# FlowControllerNChannel.net
KiCad netlist of a schematic drawn in EAGLE
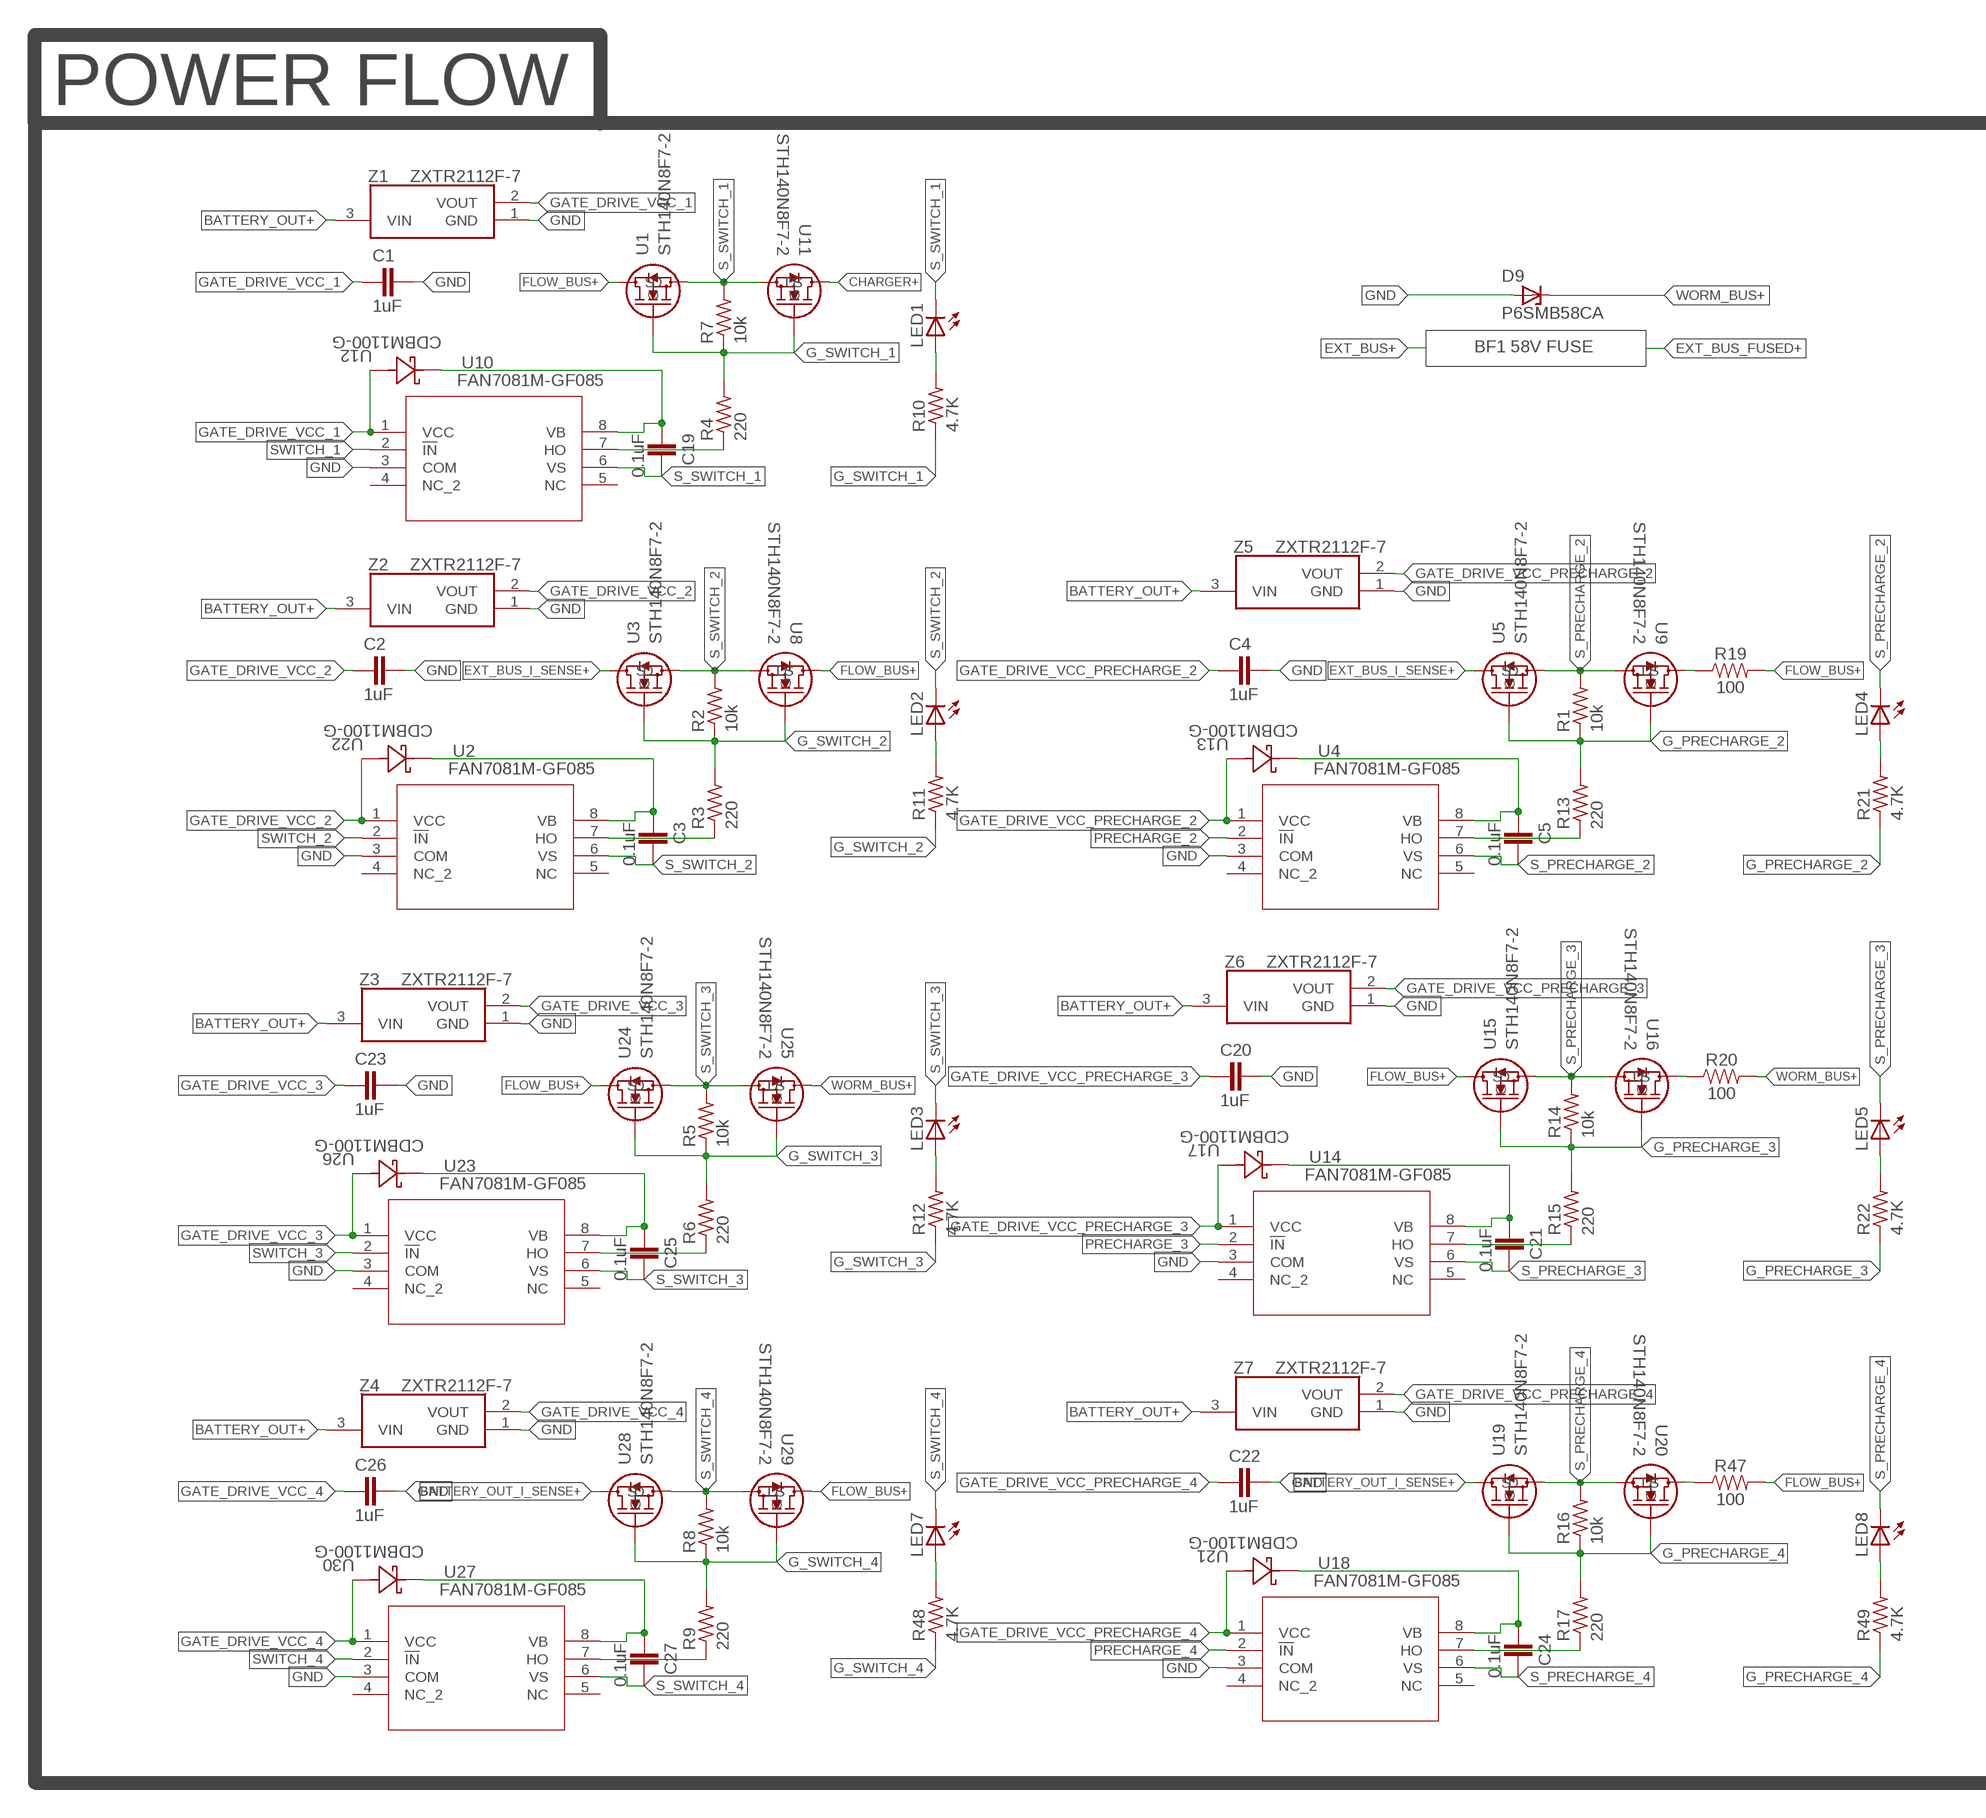
[diagram p0: schematic, sheet 1, part 1 of 2]
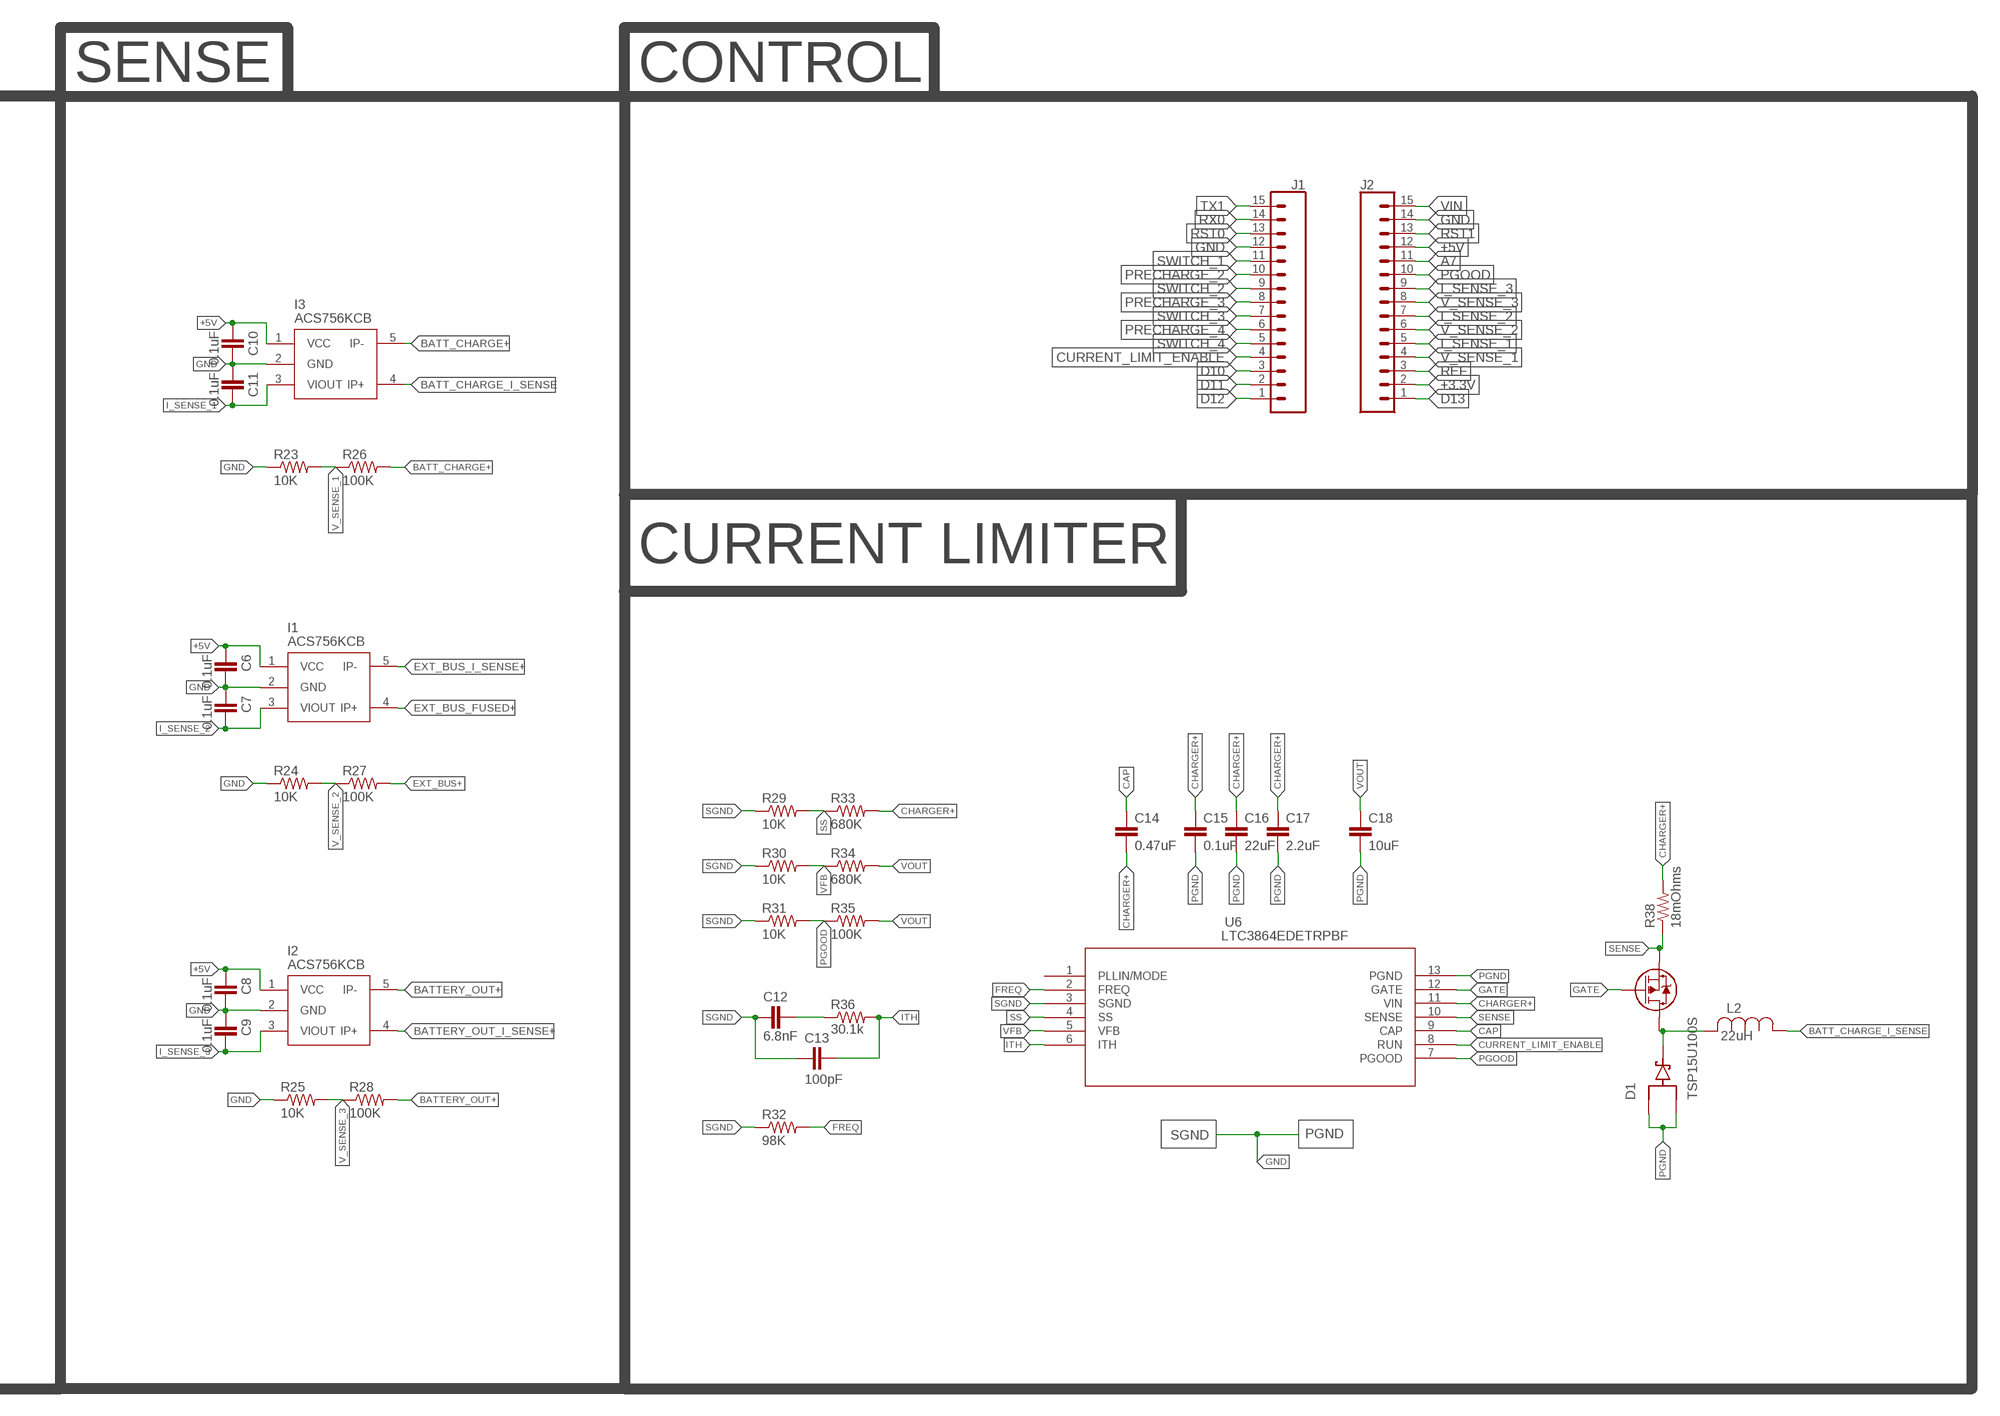
[diagram p1: schematic, sheet 1, part 2 of 2]

(export (version "E")
  (design (tool "Eeschema 10.0.6"))
  (components
    (comp (ref "C1")
      (value "1uF")
      (footprint "eagle-import:0805")
      (libsource (lib "eagle-import") (part "2.2UF-0805-25V-(+80/-20%)"))
    )
    (comp (ref "C2")
      (value "1uF")
      (footprint "eagle-import:0805")
      (libsource (lib "eagle-import") (part "2.2UF-0805-25V-(+80/-20%)"))
    )
    (comp (ref "C3")
      (value "0.1uF")
      (footprint "eagle-import:0805")
      (libsource (lib "eagle-import") (part "2.2UF-0805-25V-(+80/-20%)"))
    )
    (comp (ref "C4")
      (value "1uF")
      (footprint "eagle-import:0805")
      (libsource (lib "eagle-import") (part "2.2UF-0805-25V-(+80/-20%)"))
    )
    (comp (ref "C5")
      (value "0.1uF")
      (footprint "eagle-import:0805")
      (libsource (lib "eagle-import") (part "2.2UF-0805-25V-(+80/-20%)"))
    )
    (comp (ref "C6")
      (value "0.1uF")
      (footprint "eagle-import:0805")
      (libsource (lib "eagle-import") (part "2.2UF-0805-25V-(+80/-20%)"))
    )
    (comp (ref "C7")
      (value "0.1uF")
      (footprint "eagle-import:0805")
      (libsource (lib "eagle-import") (part "2.2UF-0805-25V-(+80/-20%)"))
    )
    (comp (ref "C8")
      (value "0.1uF")
      (footprint "eagle-import:0805")
      (libsource (lib "eagle-import") (part "2.2UF-0805-25V-(+80/-20%)"))
    )
    (comp (ref "C9")
      (value "0.1uF")
      (footprint "eagle-import:0805")
      (libsource (lib "eagle-import") (part "2.2UF-0805-25V-(+80/-20%)"))
    )
    (comp (ref "C10")
      (value "0.1uF")
      (footprint "eagle-import:0805")
      (libsource (lib "eagle-import") (part "2.2UF-0805-25V-(+80/-20%)"))
    )
    (comp (ref "C11")
      (value "0.1uF")
      (footprint "eagle-import:0805")
      (libsource (lib "eagle-import") (part "2.2UF-0805-25V-(+80/-20%)"))
    )
    (comp (ref "C12")
      (value "6.8nF")
      (footprint "eagle-import:0805")
      (libsource (lib "eagle-import") (part "2.2UF-0805-25V-(+80/-20%)"))
    )
    (comp (ref "C13")
      (value "100pF")
      (footprint "eagle-import:0805")
      (libsource (lib "eagle-import") (part "2.2UF-0805-25V-(+80/-20%)"))
    )
    (comp (ref "C14")
      (value "0.47uF")
      (footprint "eagle-import:0805")
      (libsource (lib "eagle-import") (part "2.2UF-0805-25V-(+80/-20%)"))
    )
    (comp (ref "C15")
      (value "0.1uF")
      (footprint "eagle-import:0805")
      (libsource (lib "eagle-import") (part "2.2UF-0805-25V-(+80/-20%)"))
    )
    (comp (ref "C16")
      (value "22uF")
      (footprint "eagle-import:1210")
      (libsource (lib "eagle-import") (part "10UF-1210-50V-20%"))
    )
    (comp (ref "C17")
      (value "2.2uF")
      (footprint "eagle-import:1210")
      (libsource (lib "eagle-import") (part "10UF-1210-50V-20%"))
    )
    (comp (ref "C18")
      (value "10uF")
      (footprint "eagle-import:1210")
      (libsource (lib "eagle-import") (part "10UF-1210-50V-20%"))
    )
    (comp (ref "C19")
      (value "0.1uF")
      (footprint "eagle-import:0805")
      (libsource (lib "eagle-import") (part "2.2UF-0805-25V-(+80/-20%)"))
    )
    (comp (ref "C20")
      (value "1uF")
      (footprint "eagle-import:0805")
      (libsource (lib "eagle-import") (part "2.2UF-0805-25V-(+80/-20%)"))
    )
    (comp (ref "C21")
      (value "0.1uF")
      (footprint "eagle-import:0805")
      (libsource (lib "eagle-import") (part "2.2UF-0805-25V-(+80/-20%)"))
    )
    (comp (ref "C22")
      (value "1uF")
      (footprint "eagle-import:0805")
      (libsource (lib "eagle-import") (part "2.2UF-0805-25V-(+80/-20%)"))
    )
    (comp (ref "C23")
      (value "1uF")
      (footprint "eagle-import:0805")
      (libsource (lib "eagle-import") (part "2.2UF-0805-25V-(+80/-20%)"))
    )
    (comp (ref "C24")
      (value "0.1uF")
      (footprint "eagle-import:0805")
      (libsource (lib "eagle-import") (part "2.2UF-0805-25V-(+80/-20%)"))
    )
    (comp (ref "C25")
      (value "0.1uF")
      (footprint "eagle-import:0805")
      (libsource (lib "eagle-import") (part "2.2UF-0805-25V-(+80/-20%)"))
    )
    (comp (ref "C26")
      (value "1uF")
      (footprint "eagle-import:0805")
      (libsource (lib "eagle-import") (part "2.2UF-0805-25V-(+80/-20%)"))
    )
    (comp (ref "C27")
      (value "0.1uF")
      (footprint "eagle-import:0805")
      (libsource (lib "eagle-import") (part "2.2UF-0805-25V-(+80/-20%)"))
    )
    (comp (ref "D1")
      (value "TSP15U100S")
      (footprint "eagle-import:DIO_TSP15U100S")
      (fields
        (field (name "DIGI-KEY_PART_NUMBER") "1801-TSP15U100STR-ND")
        (field (name "MF") "Taiwan Semiconductor")
      )
      (libsource (lib "eagle-import") (part "TSP15U100S"))
    )
    (comp (ref "D9")
      (value "P6SMB58CA")
      (footprint "eagle-import:DO214AA")
      (fields (field (name "MF") "ON Semiconductor") (field (name "MPN") "1SMB5913BT3G"))
      (libsource (lib "eagle-import") (part "1SMB59BT3G13"))
    )
    (comp (ref "I1")
      (value "ACS756KCB")
      (footprint "eagle-import:ACS756KCB")
      (libsource (lib "eagle-import") (part "ACS756KCB"))
    )
    (comp (ref "I2")
      (value "ACS756KCB")
      (footprint "eagle-import:ACS756KCB")
      (libsource (lib "eagle-import") (part "ACS756KCB"))
    )
    (comp (ref "I3")
      (value "ACS756KCB")
      (footprint "eagle-import:ACS756KCB")
      (libsource (lib "eagle-import") (part "ACS756KCB"))
    )
    (comp (ref "J1")
      (value "CONN_15")
      (footprint "eagle-import:1X15")
      (libsource (lib "eagle-import") (part "CONN_15"))
    )
    (comp (ref "J2")
      (value "CONN_15")
      (footprint "eagle-import:1X15")
      (fields (field (name "SPICEPREFIX") "X"))
      (libsource (lib "eagle-import") (part "CONN_15"))
    )
    (comp (ref "L2")
      (value "22uH")
      (footprint "eagle-import:IND_IHLP-4040DZ_VIS")
      (fields
        (field (name "MANUFACTURER_PART_NUMBER") "IHLP4040DZER6R8M01")
        (field (name "COPYRIGHT") "Copyright (C) 2022 Ultra Librarian. All rights reserved.")
      )
      (libsource (lib "eagle-import") (part "IHLP4040DZER6R8M01"))
    )
    (comp (ref "LED1")
      (value "LEDCHIPLED_0805")
      (footprint "eagle-import:CHIPLED_0805")
      (libsource (lib "eagle-import") (part "LEDCHIPLED_0805"))
    )
    (comp (ref "LED2")
      (value "LEDCHIPLED_0805")
      (footprint "eagle-import:CHIPLED_0805")
      (libsource (lib "eagle-import") (part "LEDCHIPLED_0805"))
    )
    (comp (ref "LED3")
      (value "LEDCHIPLED_0805")
      (footprint "eagle-import:CHIPLED_0805")
      (libsource (lib "eagle-import") (part "LEDCHIPLED_0805"))
    )
    (comp (ref "LED4")
      (value "LEDCHIPLED_0805")
      (footprint "eagle-import:CHIPLED_0805")
      (libsource (lib "eagle-import") (part "LEDCHIPLED_0805"))
    )
    (comp (ref "LED5")
      (value "LEDCHIPLED_0805")
      (footprint "eagle-import:CHIPLED_0805")
      (libsource (lib "eagle-import") (part "LEDCHIPLED_0805"))
    )
    (comp (ref "LED7")
      (value "LEDCHIPLED_0805")
      (footprint "eagle-import:CHIPLED_0805")
      (libsource (lib "eagle-import") (part "LEDCHIPLED_0805"))
    )
    (comp (ref "LED8")
      (value "LEDCHIPLED_0805")
      (footprint "eagle-import:CHIPLED_0805")
      (libsource (lib "eagle-import") (part "LEDCHIPLED_0805"))
    )
    (comp (ref "R1")
      (value "10k")
      (footprint "eagle-import:M0805")
      (libsource (lib "eagle-import") (part "R-US_M0805"))
    )
    (comp (ref "R2")
      (value "10k")
      (footprint "eagle-import:M0805")
      (libsource (lib "eagle-import") (part "R-US_M0805"))
    )
    (comp (ref "R3")
      (value "220")
      (footprint "eagle-import:M0805")
      (libsource (lib "eagle-import") (part "R-US_M0805"))
    )
    (comp (ref "R4")
      (value "220")
      (footprint "eagle-import:M0805")
      (libsource (lib "eagle-import") (part "R-US_M0805"))
    )
    (comp (ref "R5")
      (value "10k")
      (footprint "eagle-import:M0805")
      (libsource (lib "eagle-import") (part "R-US_M0805"))
    )
    (comp (ref "R6")
      (value "220")
      (footprint "eagle-import:M0805")
      (libsource (lib "eagle-import") (part "R-US_M0805"))
    )
    (comp (ref "R7")
      (value "10k")
      (footprint "eagle-import:M0805")
      (libsource (lib "eagle-import") (part "R-US_M0805"))
    )
    (comp (ref "R8")
      (value "10k")
      (footprint "eagle-import:M0805")
      (libsource (lib "eagle-import") (part "R-US_M0805"))
    )
    (comp (ref "R9")
      (value "220")
      (footprint "eagle-import:M0805")
      (libsource (lib "eagle-import") (part "R-US_M0805"))
    )
    (comp (ref "R10")
      (value "4.7K")
      (footprint "eagle-import:M0805")
      (libsource (lib "eagle-import") (part "R-US_M0805"))
    )
    (comp (ref "R11")
      (value "4.7K")
      (footprint "eagle-import:M0805")
      (libsource (lib "eagle-import") (part "R-US_M0805"))
    )
    (comp (ref "R12")
      (value "4.7K")
      (footprint "eagle-import:M0805")
      (libsource (lib "eagle-import") (part "R-US_M0805"))
    )
    (comp (ref "R13")
      (value "220")
      (footprint "eagle-import:M0805")
      (libsource (lib "eagle-import") (part "R-US_M0805"))
    )
    (comp (ref "R14")
      (value "10k")
      (footprint "eagle-import:M0805")
      (libsource (lib "eagle-import") (part "R-US_M0805"))
    )
    (comp (ref "R15")
      (value "220")
      (footprint "eagle-import:M0805")
      (libsource (lib "eagle-import") (part "R-US_M0805"))
    )
    (comp (ref "R16")
      (value "10k")
      (footprint "eagle-import:M0805")
      (libsource (lib "eagle-import") (part "R-US_M0805"))
    )
    (comp (ref "R17")
      (value "220")
      (footprint "eagle-import:M0805")
      (libsource (lib "eagle-import") (part "R-US_M0805"))
    )
    (comp (ref "R19")
      (value "100")
      (footprint "eagle-import:2512")
      (libsource (lib "eagle-import") (part "0.05OHM-2512-3W-1%"))
    )
    (comp (ref "R20")
      (value "100")
      (footprint "eagle-import:2512")
      (libsource (lib "eagle-import") (part "0.05OHM-2512-3W-1%"))
    )
    (comp (ref "R21")
      (value "4.7K")
      (footprint "eagle-import:M0805")
      (libsource (lib "eagle-import") (part "R-US_M0805"))
    )
    (comp (ref "R22")
      (value "4.7K")
      (footprint "eagle-import:M0805")
      (libsource (lib "eagle-import") (part "R-US_M0805"))
    )
    (comp (ref "R23")
      (value "10K")
      (footprint "eagle-import:M0805")
      (libsource (lib "eagle-import") (part "R-US_M0805"))
    )
    (comp (ref "R24")
      (value "10K")
      (footprint "eagle-import:M0805")
      (libsource (lib "eagle-import") (part "R-US_M0805"))
    )
    (comp (ref "R25")
      (value "10K")
      (footprint "eagle-import:M0805")
      (libsource (lib "eagle-import") (part "R-US_M0805"))
    )
    (comp (ref "R26")
      (value "100K")
      (footprint "eagle-import:M0805")
      (libsource (lib "eagle-import") (part "R-US_M0805"))
    )
    (comp (ref "R27")
      (value "100K")
      (footprint "eagle-import:M0805")
      (libsource (lib "eagle-import") (part "R-US_M0805"))
    )
    (comp (ref "R28")
      (value "100K")
      (footprint "eagle-import:M0805")
      (libsource (lib "eagle-import") (part "R-US_M0805"))
    )
    (comp (ref "R29")
      (value "10K")
      (footprint "eagle-import:M0805")
      (libsource (lib "eagle-import") (part "R-US_M0805"))
    )
    (comp (ref "R30")
      (value "10K")
      (footprint "eagle-import:M0805")
      (libsource (lib "eagle-import") (part "R-US_M0805"))
    )
    (comp (ref "R31")
      (value "10K")
      (footprint "eagle-import:M0805")
      (libsource (lib "eagle-import") (part "R-US_M0805"))
    )
    (comp (ref "R32")
      (value "98K")
      (footprint "eagle-import:M0805")
      (libsource (lib "eagle-import") (part "R-US_M0805"))
    )
    (comp (ref "R33")
      (value "680K")
      (footprint "eagle-import:M0805")
      (libsource (lib "eagle-import") (part "R-US_M0805"))
    )
    (comp (ref "R34")
      (value "680K")
      (footprint "eagle-import:M0805")
      (libsource (lib "eagle-import") (part "R-US_M0805"))
    )
    (comp (ref "R35")
      (value "100K")
      (footprint "eagle-import:M0805")
      (libsource (lib "eagle-import") (part "R-US_M0805"))
    )
    (comp (ref "R36")
      (value "30.1k")
      (footprint "eagle-import:M0805")
      (libsource (lib "eagle-import") (part "R-US_M0805"))
    )
    (comp (ref "R37")
      (value "RSJ250P10TL")
      (footprint "eagle-import:TRANS_R5009FNJ_ROM")
      (fields (field (name "COPYRIGHT") "Copyright (C) 2022 Ultra Librarian. All rights reserved."))
      (libsource (lib "eagle-import") (part "RSJ250P10TL"))
    )
    (comp (ref "R38")
      (value "18mOhms")
      (footprint "eagle-import:M0805")
      (libsource (lib "eagle-import") (part "R-US_M0805"))
    )
    (comp (ref "R47")
      (value "100")
      (footprint "eagle-import:2512")
      (libsource (lib "eagle-import") (part "0.05OHM-2512-3W-1%"))
    )
    (comp (ref "R48")
      (value "4.7K")
      (footprint "eagle-import:M0805")
      (libsource (lib "eagle-import") (part "R-US_M0805"))
    )
    (comp (ref "R49")
      (value "4.7K")
      (footprint "eagle-import:M0805")
      (libsource (lib "eagle-import") (part "R-US_M0805"))
    )
    (comp (ref "U1")
      (value "STH140N8F7-2")
      (footprint "eagle-import:HPAK_0N8F7-2_STM")
      (fields (field (name "COPYRIGHT") "Copyright (C) 2022 Ultra Librarian. All rights reserved."))
      (libsource (lib "eagle-import") (part "STH140N8F7-2"))
    )
    (comp (ref "U2")
      (value "FAN7081M-GF085")
      (footprint "eagle-import:SOIC8_3P9X4P9_ONS")
      (fields (field (name "COPYRIGHT") "Copyright (C) 2022 Ultra Librarian. All rights reserved."))
      (libsource (lib "eagle-import") (part "FAN7081M-GF085"))
    )
    (comp (ref "U3")
      (value "STH140N8F7-2")
      (footprint "eagle-import:HPAK_0N8F7-2_STM")
      (fields (field (name "COPYRIGHT") "Copyright (C) 2022 Ultra Librarian. All rights reserved."))
      (libsource (lib "eagle-import") (part "STH140N8F7-2"))
    )
    (comp (ref "U4")
      (value "FAN7081M-GF085")
      (footprint "eagle-import:SOIC8_3P9X4P9_ONS")
      (fields (field (name "COPYRIGHT") "Copyright (C) 2022 Ultra Librarian. All rights reserved."))
      (libsource (lib "eagle-import") (part "FAN7081M-GF085"))
    )
    (comp (ref "U5")
      (value "STH140N8F7-2")
      (footprint "eagle-import:HPAK_0N8F7-2_STM")
      (fields (field (name "COPYRIGHT") "Copyright (C) 2022 Ultra Librarian. All rights reserved."))
      (libsource (lib "eagle-import") (part "STH140N8F7-2"))
    )
    (comp (ref "U6")
      (value "LTC3864EDETRPBF")
      (footprint "eagle-import:DFN-12_DE")
      (fields
        (field (name "DIGI-KEY_PART_NUMBER") "161-LTC3864EDE#TRPBFTR-ND")
        (field (name "MF") "Analog Devices")
        (field (name "MP") "LTC3864EDE#TRPBF")
      )
      (libsource (lib "eagle-import") (part "LTC3864EDETRPBF"))
    )
    (comp (ref "U8")
      (value "STH140N8F7-2")
      (footprint "eagle-import:HPAK_0N8F7-2_STM")
      (fields (field (name "COPYRIGHT") "Copyright (C) 2022 Ultra Librarian. All rights reserved."))
      (libsource (lib "eagle-import") (part "STH140N8F7-2"))
    )
    (comp (ref "U9")
      (value "STH140N8F7-2")
      (footprint "eagle-import:HPAK_0N8F7-2_STM")
      (fields (field (name "COPYRIGHT") "Copyright (C) 2022 Ultra Librarian. All rights reserved."))
      (libsource (lib "eagle-import") (part "STH140N8F7-2"))
    )
    (comp (ref "U10")
      (value "FAN7081M-GF085")
      (footprint "eagle-import:SOIC8_3P9X4P9_ONS")
      (fields (field (name "COPYRIGHT") "Copyright (C) 2022 Ultra Librarian. All rights reserved."))
      (libsource (lib "eagle-import") (part "FAN7081M-GF085"))
    )
    (comp (ref "U11")
      (value "STH140N8F7-2")
      (footprint "eagle-import:HPAK_0N8F7-2_STM")
      (fields (field (name "COPYRIGHT") "Copyright (C) 2022 Ultra Librarian. All rights reserved."))
      (libsource (lib "eagle-import") (part "STH140N8F7-2"))
    )
    (comp (ref "U12")
      (value "CDBM1100-G")
      (footprint "eagle-import:CDBM")
      (fields (field (name "COPYRIGHT") "Copyright (C) 2022 Ultra Librarian. All rights reserved."))
      (libsource (lib "eagle-import") (part "CDBM1100-G"))
    )
    (comp (ref "U13")
      (value "CDBM1100-G")
      (footprint "eagle-import:CDBM")
      (fields (field (name "COPYRIGHT") "Copyright (C) 2022 Ultra Librarian. All rights reserved."))
      (libsource (lib "eagle-import") (part "CDBM1100-G"))
    )
    (comp (ref "U14")
      (value "FAN7081M-GF085")
      (footprint "eagle-import:SOIC8_3P9X4P9_ONS")
      (fields (field (name "COPYRIGHT") "Copyright (C) 2022 Ultra Librarian. All rights reserved."))
      (libsource (lib "eagle-import") (part "FAN7081M-GF085"))
    )
    (comp (ref "U15")
      (value "STH140N8F7-2")
      (footprint "eagle-import:HPAK_0N8F7-2_STM")
      (fields (field (name "COPYRIGHT") "Copyright (C) 2022 Ultra Librarian. All rights reserved."))
      (libsource (lib "eagle-import") (part "STH140N8F7-2"))
    )
    (comp (ref "U16")
      (value "STH140N8F7-2")
      (footprint "eagle-import:HPAK_0N8F7-2_STM")
      (fields (field (name "COPYRIGHT") "Copyright (C) 2022 Ultra Librarian. All rights reserved."))
      (libsource (lib "eagle-import") (part "STH140N8F7-2"))
    )
    (comp (ref "U17")
      (value "CDBM1100-G")
      (footprint "eagle-import:CDBM")
      (fields (field (name "COPYRIGHT") "Copyright (C) 2022 Ultra Librarian. All rights reserved."))
      (libsource (lib "eagle-import") (part "CDBM1100-G"))
    )
    (comp (ref "U18")
      (value "FAN7081M-GF085")
      (footprint "eagle-import:SOIC8_3P9X4P9_ONS")
      (fields (field (name "COPYRIGHT") "Copyright (C) 2022 Ultra Librarian. All rights reserved."))
      (libsource (lib "eagle-import") (part "FAN7081M-GF085"))
    )
    (comp (ref "U19")
      (value "STH140N8F7-2")
      (footprint "eagle-import:HPAK_0N8F7-2_STM")
      (fields (field (name "COPYRIGHT") "Copyright (C) 2022 Ultra Librarian. All rights reserved."))
      (libsource (lib "eagle-import") (part "STH140N8F7-2"))
    )
    (comp (ref "U20")
      (value "STH140N8F7-2")
      (footprint "eagle-import:HPAK_0N8F7-2_STM")
      (fields (field (name "COPYRIGHT") "Copyright (C) 2022 Ultra Librarian. All rights reserved."))
      (libsource (lib "eagle-import") (part "STH140N8F7-2"))
    )
    (comp (ref "U21")
      (value "CDBM1100-G")
      (footprint "eagle-import:CDBM")
      (fields (field (name "COPYRIGHT") "Copyright (C) 2022 Ultra Librarian. All rights reserved."))
      (libsource (lib "eagle-import") (part "CDBM1100-G"))
    )
    (comp (ref "U22")
      (value "CDBM1100-G")
      (footprint "eagle-import:CDBM")
      (fields (field (name "COPYRIGHT") "Copyright (C) 2022 Ultra Librarian. All rights reserved."))
      (libsource (lib "eagle-import") (part "CDBM1100-G"))
    )
    (comp (ref "U23")
      (value "FAN7081M-GF085")
      (footprint "eagle-import:SOIC8_3P9X4P9_ONS")
      (fields (field (name "COPYRIGHT") "Copyright (C) 2022 Ultra Librarian. All rights reserved."))
      (libsource (lib "eagle-import") (part "FAN7081M-GF085"))
    )
    (comp (ref "U24")
      (value "STH140N8F7-2")
      (footprint "eagle-import:HPAK_0N8F7-2_STM")
      (fields (field (name "COPYRIGHT") "Copyright (C) 2022 Ultra Librarian. All rights reserved."))
      (libsource (lib "eagle-import") (part "STH140N8F7-2"))
    )
    (comp (ref "U25")
      (value "STH140N8F7-2")
      (footprint "eagle-import:HPAK_0N8F7-2_STM")
      (fields (field (name "COPYRIGHT") "Copyright (C) 2022 Ultra Librarian. All rights reserved."))
      (libsource (lib "eagle-import") (part "STH140N8F7-2"))
    )
    (comp (ref "U26")
      (value "CDBM1100-G")
      (footprint "eagle-import:CDBM")
      (fields (field (name "COPYRIGHT") "Copyright (C) 2022 Ultra Librarian. All rights reserved."))
      (libsource (lib "eagle-import") (part "CDBM1100-G"))
    )
    (comp (ref "U27")
      (value "FAN7081M-GF085")
      (footprint "eagle-import:SOIC8_3P9X4P9_ONS")
      (fields (field (name "COPYRIGHT") "Copyright (C) 2022 Ultra Librarian. All rights reserved."))
      (libsource (lib "eagle-import") (part "FAN7081M-GF085"))
    )
    (comp (ref "U28")
      (value "STH140N8F7-2")
      (footprint "eagle-import:HPAK_0N8F7-2_STM")
      (fields (field (name "COPYRIGHT") "Copyright (C) 2022 Ultra Librarian. All rights reserved."))
      (libsource (lib "eagle-import") (part "STH140N8F7-2"))
    )
    (comp (ref "U29")
      (value "STH140N8F7-2")
      (footprint "eagle-import:HPAK_0N8F7-2_STM")
      (fields (field (name "COPYRIGHT") "Copyright (C) 2022 Ultra Librarian. All rights reserved."))
      (libsource (lib "eagle-import") (part "STH140N8F7-2"))
    )
    (comp (ref "U30")
      (value "CDBM1100-G")
      (footprint "eagle-import:CDBM")
      (fields (field (name "COPYRIGHT") "Copyright (C) 2022 Ultra Librarian. All rights reserved."))
      (libsource (lib "eagle-import") (part "CDBM1100-G"))
    )
    (comp (ref "Z1")
      (value "ZXTR2112F-7")
      (footprint "eagle-import:SOT96P240X110-3N")
      (fields (field (name "MOUSER_PART_NUMBER") "621-ZXTR2112F-7"))
      (libsource (lib "eagle-import") (part "ZXTR2112F-7"))
    )
    (comp (ref "Z2")
      (value "ZXTR2112F-7")
      (footprint "eagle-import:SOT96P240X110-3N")
      (fields (field (name "MOUSER_PART_NUMBER") "621-ZXTR2112F-7"))
      (libsource (lib "eagle-import") (part "ZXTR2112F-7"))
    )
    (comp (ref "Z3")
      (value "ZXTR2112F-7")
      (footprint "eagle-import:SOT96P240X110-3N")
      (fields (field (name "MOUSER_PART_NUMBER") "621-ZXTR2112F-7"))
      (libsource (lib "eagle-import") (part "ZXTR2112F-7"))
    )
    (comp (ref "Z4")
      (value "ZXTR2112F-7")
      (footprint "eagle-import:SOT96P240X110-3N")
      (fields (field (name "MOUSER_PART_NUMBER") "621-ZXTR2112F-7"))
      (libsource (lib "eagle-import") (part "ZXTR2112F-7"))
    )
    (comp (ref "Z5")
      (value "ZXTR2112F-7")
      (footprint "eagle-import:SOT96P240X110-3N")
      (fields (field (name "MOUSER_PART_NUMBER") "621-ZXTR2112F-7"))
      (libsource (lib "eagle-import") (part "ZXTR2112F-7"))
    )
    (comp (ref "Z6")
      (value "ZXTR2112F-7")
      (footprint "eagle-import:SOT96P240X110-3N")
      (fields (field (name "MOUSER_PART_NUMBER") "621-ZXTR2112F-7"))
      (libsource (lib "eagle-import") (part "ZXTR2112F-7"))
    )
    (comp (ref "Z7")
      (value "ZXTR2112F-7")
      (footprint "eagle-import:SOT96P240X110-3N")
      (fields (field (name "MOUSER_PART_NUMBER") "621-ZXTR2112F-7"))
      (libsource (lib "eagle-import") (part "ZXTR2112F-7"))
    )
  )
  (nets
    (net (code "1") (name "+3.3V") (class "Default")
      (node (ref "J2") (pin "2") (pinfunction "2_2") (pintype "passive"))
    )
    (net (code "2") (name "+5V") (class "Default")
      (node (ref "C10") (pin "1") (pinfunction "1_1") (pintype "passive"))
      (node (ref "C6") (pin "1") (pinfunction "1_1") (pintype "passive"))
      (node (ref "C8") (pin "1") (pinfunction "1_1") (pintype "passive"))
      (node (ref "I1") (pin "1") (pinfunction "VCC_1") (pintype "bidirectional"))
      (node (ref "I2") (pin "1") (pinfunction "VCC_1") (pintype "bidirectional"))
      (node (ref "I3") (pin "1") (pinfunction "VCC_1") (pintype "bidirectional"))
      (node (ref "J2") (pin "12") (pinfunction "12_12") (pintype "passive"))
    )
    (net (code "3") (name "A7") (class "Default")
      (node (ref "J2") (pin "11") (pinfunction "11_11") (pintype "passive"))
    )
    (net (code "4") (name "BATTERY_OUT+") (class "Default")
      (node (ref "I2") (pin "5") (pinfunction "IP-_5") (pintype "bidirectional"))
      (node (ref "R28") (pin "2") (pinfunction "2_2") (pintype "passive"))
      (node (ref "Z1") (pin "3") (pinfunction "VIN_3") (pintype "bidirectional"))
      (node (ref "Z2") (pin "3") (pinfunction "VIN_3") (pintype "bidirectional"))
      (node (ref "Z3") (pin "3") (pinfunction "VIN_3") (pintype "bidirectional"))
      (node (ref "Z4") (pin "3") (pinfunction "VIN_3") (pintype "bidirectional"))
      (node (ref "Z5") (pin "3") (pinfunction "VIN_3") (pintype "bidirectional"))
      (node (ref "Z6") (pin "3") (pinfunction "VIN_3") (pintype "bidirectional"))
      (node (ref "Z7") (pin "3") (pinfunction "VIN_3") (pintype "bidirectional"))
    )
    (net (code "5") (name "BATTERY_OUT_I_SENSE+") (class "Default")
      (node (ref "I2") (pin "4") (pinfunction "IP+_4") (pintype "bidirectional"))
      (node (ref "U19") (pin "2") (pinfunction "D_2") (pintype "passive"))
      (node (ref "U28") (pin "2") (pinfunction "D_2") (pintype "passive"))
    )
    (net (code "6") (name "BATT_CHARGE+") (class "Default")
      (node (ref "I3") (pin "5") (pinfunction "IP-_5") (pintype "bidirectional"))
      (node (ref "R26") (pin "2") (pinfunction "2_2") (pintype "passive"))
    )
    (net (code "7") (name "BATT_CHARGE_I_SENSE") (class "Default")
      (node (ref "I3") (pin "4") (pinfunction "IP+_4") (pintype "bidirectional"))
      (node (ref "L2") (pin "1") (pinfunction "1_1") (pintype "passive"))
    )
    (net (code "8") (name "CAP") (class "Default")
      (node (ref "C14") (pin "1") (pinfunction "1_1") (pintype "passive"))
      (node (ref "U6") (pin "9") (pinfunction "CAP_9") (pintype "passive"))
    )
    (net (code "9") (name "CHARGER+") (class "Default")
      (node (ref "C14") (pin "2") (pinfunction "2_2") (pintype "passive"))
      (node (ref "C15") (pin "1") (pinfunction "1_1") (pintype "passive"))
      (node (ref "C16") (pin "1") (pinfunction "1_1") (pintype "passive"))
      (node (ref "C17") (pin "1") (pinfunction "1_1") (pintype "passive"))
      (node (ref "R33") (pin "2") (pinfunction "2_2") (pintype "passive"))
      (node (ref "R38") (pin "2") (pinfunction "2_2") (pintype "passive"))
      (node (ref "U11") (pin "2") (pinfunction "D_2") (pintype "passive"))
      (node (ref "U6") (pin "11") (pinfunction "VIN_11") (pintype "input"))
    )
    (net (code "10") (name "CURRENT_LIMIT_ENABLE") (class "Default")
      (node (ref "J1") (pin "4") (pinfunction "4_4") (pintype "passive"))
      (node (ref "U6") (pin "8") (pinfunction "RUN_8") (pintype "input"))
    )
    (net (code "11") (name "D10") (class "Default")
      (node (ref "J1") (pin "3") (pinfunction "3_3") (pintype "passive"))
    )
    (net (code "12") (name "D11") (class "Default")
      (node (ref "J1") (pin "2") (pinfunction "2_2") (pintype "passive"))
    )
    (net (code "13") (name "D12") (class "Default")
      (node (ref "J1") (pin "1") (pinfunction "1_1") (pintype "passive"))
    )
    (net (code "14") (name "D13") (class "Default")
      (node (ref "J2") (pin "1") (pinfunction "1_1") (pintype "passive"))
    )
    (net (code "15") (name "EXT_BUS+") (class "Default")
      (node (ref "R27") (pin "2") (pinfunction "2_2") (pintype "passive"))
    )
    (net (code "16") (name "EXT_BUS_FUSED+") (class "Default")
      (node (ref "I1") (pin "4") (pinfunction "IP+_4") (pintype "bidirectional"))
    )
    (net (code "17") (name "EXT_BUS_I_SENSE+") (class "Default")
      (node (ref "I1") (pin "5") (pinfunction "IP-_5") (pintype "bidirectional"))
      (node (ref "U3") (pin "2") (pinfunction "D_2") (pintype "passive"))
      (node (ref "U5") (pin "2") (pinfunction "D_2") (pintype "passive"))
    )
    (net (code "18") (name "FLOW_BUS+") (class "Default")
      (node (ref "R19") (pin "P$2") (pinfunction "2_P$2") (pintype "passive"))
      (node (ref "R47") (pin "P$2") (pinfunction "2_P$2") (pintype "passive"))
      (node (ref "U1") (pin "2") (pinfunction "D_2") (pintype "passive"))
      (node (ref "U15") (pin "2") (pinfunction "D_2") (pintype "passive"))
      (node (ref "U24") (pin "2") (pinfunction "D_2") (pintype "passive"))
      (node (ref "U29") (pin "2") (pinfunction "D_2") (pintype "passive"))
      (node (ref "U8") (pin "2") (pinfunction "D_2") (pintype "passive"))
    )
    (net (code "19") (name "FREQ") (class "Default")
      (node (ref "R32") (pin "2") (pinfunction "2_2") (pintype "passive"))
      (node (ref "U6") (pin "2") (pinfunction "FREQ_2") (pintype "input"))
    )
    (net (code "20") (name "GATE") (class "Default")
      (node (ref "R37") (pin "1") (pinfunction "1_1") (pintype "passive"))
      (node (ref "U6") (pin "12") (pinfunction "GATE_12") (pintype "output"))
    )
    (net (code "21") (name "GATE_DRIVE_VCC_1") (class "Default")
      (node (ref "C1") (pin "1") (pinfunction "1_1") (pintype "passive"))
      (node (ref "U10") (pin "1") (pinfunction "VCC_1") (pintype "power_in"))
      (node (ref "U12") (pin "2") (pinfunction "2_2") (pintype "passive"))
      (node (ref "Z1") (pin "2") (pinfunction "VOUT_2") (pintype "bidirectional"))
    )
    (net (code "22") (name "GATE_DRIVE_VCC_2") (class "Default")
      (node (ref "C2") (pin "1") (pinfunction "1_1") (pintype "passive"))
      (node (ref "U2") (pin "1") (pinfunction "VCC_1") (pintype "power_in"))
      (node (ref "U22") (pin "2") (pinfunction "2_2") (pintype "passive"))
      (node (ref "Z2") (pin "2") (pinfunction "VOUT_2") (pintype "bidirectional"))
    )
    (net (code "23") (name "GATE_DRIVE_VCC_3") (class "Default")
      (node (ref "C23") (pin "1") (pinfunction "1_1") (pintype "passive"))
      (node (ref "U23") (pin "1") (pinfunction "VCC_1") (pintype "power_in"))
      (node (ref "U26") (pin "2") (pinfunction "2_2") (pintype "passive"))
      (node (ref "Z3") (pin "2") (pinfunction "VOUT_2") (pintype "bidirectional"))
    )
    (net (code "24") (name "GATE_DRIVE_VCC_4") (class "Default")
      (node (ref "C26") (pin "1") (pinfunction "1_1") (pintype "passive"))
      (node (ref "U27") (pin "1") (pinfunction "VCC_1") (pintype "power_in"))
      (node (ref "U30") (pin "2") (pinfunction "2_2") (pintype "passive"))
      (node (ref "Z4") (pin "2") (pinfunction "VOUT_2") (pintype "bidirectional"))
    )
    (net (code "25") (name "GATE_DRIVE_VCC_PRECHARGE_2") (class "Default")
      (node (ref "C4") (pin "1") (pinfunction "1_1") (pintype "passive"))
      (node (ref "U13") (pin "2") (pinfunction "2_2") (pintype "passive"))
      (node (ref "U4") (pin "1") (pinfunction "VCC_1") (pintype "power_in"))
      (node (ref "Z5") (pin "2") (pinfunction "VOUT_2") (pintype "bidirectional"))
    )
    (net (code "26") (name "GATE_DRIVE_VCC_PRECHARGE_3") (class "Default")
      (node (ref "C20") (pin "1") (pinfunction "1_1") (pintype "passive"))
      (node (ref "U14") (pin "1") (pinfunction "VCC_1") (pintype "power_in"))
      (node (ref "U17") (pin "2") (pinfunction "2_2") (pintype "passive"))
      (node (ref "Z6") (pin "2") (pinfunction "VOUT_2") (pintype "bidirectional"))
    )
    (net (code "27") (name "GATE_DRIVE_VCC_PRECHARGE_4") (class "Default")
      (node (ref "C22") (pin "1") (pinfunction "1_1") (pintype "passive"))
      (node (ref "U18") (pin "1") (pinfunction "VCC_1") (pintype "power_in"))
      (node (ref "U21") (pin "2") (pinfunction "2_2") (pintype "passive"))
      (node (ref "Z7") (pin "2") (pinfunction "VOUT_2") (pintype "bidirectional"))
    )
    (net (code "28") (name "GND") (class "Default")
      (node (ref "C1") (pin "2") (pinfunction "2_2") (pintype "passive"))
      (node (ref "C10") (pin "2") (pinfunction "2_2") (pintype "passive"))
      (node (ref "C11") (pin "1") (pinfunction "1_1") (pintype "passive"))
      (node (ref "C2") (pin "2") (pinfunction "2_2") (pintype "passive"))
      (node (ref "C20") (pin "2") (pinfunction "2_2") (pintype "passive"))
      (node (ref "C22") (pin "2") (pinfunction "2_2") (pintype "passive"))
      (node (ref "C23") (pin "2") (pinfunction "2_2") (pintype "passive"))
      (node (ref "C26") (pin "2") (pinfunction "2_2") (pintype "passive"))
      (node (ref "C4") (pin "2") (pinfunction "2_2") (pintype "passive"))
      (node (ref "C6") (pin "2") (pinfunction "2_2") (pintype "passive"))
      (node (ref "C7") (pin "1") (pinfunction "1_1") (pintype "passive"))
      (node (ref "C8") (pin "2") (pinfunction "2_2") (pintype "passive"))
      (node (ref "C9") (pin "1") (pinfunction "1_1") (pintype "passive"))
      (node (ref "D9") (pin "A") (pinfunction "A_A") (pintype "passive"))
      (node (ref "I1") (pin "2") (pinfunction "GND_2") (pintype "bidirectional"))
      (node (ref "I2") (pin "2") (pinfunction "GND_2") (pintype "bidirectional"))
      (node (ref "I3") (pin "2") (pinfunction "GND_2") (pintype "bidirectional"))
      (node (ref "J1") (pin "12") (pinfunction "12_12") (pintype "passive"))
      (node (ref "J2") (pin "14") (pinfunction "14_14") (pintype "passive"))
      (node (ref "R23") (pin "1") (pinfunction "1_1") (pintype "passive"))
      (node (ref "R24") (pin "1") (pinfunction "1_1") (pintype "passive"))
      (node (ref "R25") (pin "1") (pinfunction "1_1") (pintype "passive"))
      (node (ref "U10") (pin "3") (pinfunction "COM_3") (pintype "passive"))
      (node (ref "U14") (pin "3") (pinfunction "COM_3") (pintype "passive"))
      (node (ref "U18") (pin "3") (pinfunction "COM_3") (pintype "passive"))
      (node (ref "U2") (pin "3") (pinfunction "COM_3") (pintype "passive"))
      (node (ref "U23") (pin "3") (pinfunction "COM_3") (pintype "passive"))
      (node (ref "U27") (pin "3") (pinfunction "COM_3") (pintype "passive"))
      (node (ref "U4") (pin "3") (pinfunction "COM_3") (pintype "passive"))
      (node (ref "Z1") (pin "1") (pinfunction "GND_1") (pintype "bidirectional"))
      (node (ref "Z2") (pin "1") (pinfunction "GND_1") (pintype "bidirectional"))
      (node (ref "Z3") (pin "1") (pinfunction "GND_1") (pintype "bidirectional"))
      (node (ref "Z4") (pin "1") (pinfunction "GND_1") (pintype "bidirectional"))
      (node (ref "Z5") (pin "1") (pinfunction "GND_1") (pintype "bidirectional"))
      (node (ref "Z6") (pin "1") (pinfunction "GND_1") (pintype "bidirectional"))
      (node (ref "Z7") (pin "1") (pinfunction "GND_1") (pintype "bidirectional"))
    )
    (net (code "29") (name "G_PRECHARGE_2") (class "Default")
      (node (ref "R1") (pin "1") (pinfunction "1_1") (pintype "passive"))
      (node (ref "R13") (pin "2") (pinfunction "2_2") (pintype "passive"))
      (node (ref "R21") (pin "1") (pinfunction "1_1") (pintype "passive"))
      (node (ref "U5") (pin "1") (pinfunction "G_1") (pintype "passive"))
      (node (ref "U9") (pin "1") (pinfunction "G_1") (pintype "passive"))
    )
    (net (code "30") (name "G_PRECHARGE_3") (class "Default")
      (node (ref "R14") (pin "1") (pinfunction "1_1") (pintype "passive"))
      (node (ref "R15") (pin "2") (pinfunction "2_2") (pintype "passive"))
      (node (ref "R22") (pin "1") (pinfunction "1_1") (pintype "passive"))
      (node (ref "U15") (pin "1") (pinfunction "G_1") (pintype "passive"))
      (node (ref "U16") (pin "1") (pinfunction "G_1") (pintype "passive"))
    )
    (net (code "31") (name "G_PRECHARGE_4") (class "Default")
      (node (ref "R16") (pin "1") (pinfunction "1_1") (pintype "passive"))
      (node (ref "R17") (pin "2") (pinfunction "2_2") (pintype "passive"))
      (node (ref "R49") (pin "1") (pinfunction "1_1") (pintype "passive"))
      (node (ref "U19") (pin "1") (pinfunction "G_1") (pintype "passive"))
      (node (ref "U20") (pin "1") (pinfunction "G_1") (pintype "passive"))
    )
    (net (code "32") (name "G_SWITCH_1") (class "Default")
      (node (ref "R10") (pin "1") (pinfunction "1_1") (pintype "passive"))
      (node (ref "R4") (pin "2") (pinfunction "2_2") (pintype "passive"))
      (node (ref "R7") (pin "1") (pinfunction "1_1") (pintype "passive"))
      (node (ref "U1") (pin "1") (pinfunction "G_1") (pintype "passive"))
      (node (ref "U11") (pin "1") (pinfunction "G_1") (pintype "passive"))
    )
    (net (code "33") (name "G_SWITCH_2") (class "Default")
      (node (ref "R11") (pin "1") (pinfunction "1_1") (pintype "passive"))
      (node (ref "R2") (pin "1") (pinfunction "1_1") (pintype "passive"))
      (node (ref "R3") (pin "2") (pinfunction "2_2") (pintype "passive"))
      (node (ref "U3") (pin "1") (pinfunction "G_1") (pintype "passive"))
      (node (ref "U8") (pin "1") (pinfunction "G_1") (pintype "passive"))
    )
    (net (code "34") (name "G_SWITCH_3") (class "Default")
      (node (ref "R12") (pin "1") (pinfunction "1_1") (pintype "passive"))
      (node (ref "R5") (pin "1") (pinfunction "1_1") (pintype "passive"))
      (node (ref "R6") (pin "2") (pinfunction "2_2") (pintype "passive"))
      (node (ref "U24") (pin "1") (pinfunction "G_1") (pintype "passive"))
      (node (ref "U25") (pin "1") (pinfunction "G_1") (pintype "passive"))
    )
    (net (code "35") (name "G_SWITCH_4") (class "Default")
      (node (ref "R48") (pin "1") (pinfunction "1_1") (pintype "passive"))
      (node (ref "R8") (pin "1") (pinfunction "1_1") (pintype "passive"))
      (node (ref "R9") (pin "2") (pinfunction "2_2") (pintype "passive"))
      (node (ref "U28") (pin "1") (pinfunction "G_1") (pintype "passive"))
      (node (ref "U29") (pin "1") (pinfunction "G_1") (pintype "passive"))
    )
    (net (code "36") (name "ITH") (class "Default")
      (node (ref "C13") (pin "2") (pinfunction "2_2") (pintype "passive"))
      (node (ref "R36") (pin "2") (pinfunction "2_2") (pintype "passive"))
      (node (ref "U6") (pin "6") (pinfunction "ITH_6") (pintype "output"))
    )
    (net (code "37") (name "I_SENSE_1") (class "Default")
      (node (ref "C11") (pin "2") (pinfunction "2_2") (pintype "passive"))
      (node (ref "I3") (pin "3") (pinfunction "VIOUT_3") (pintype "bidirectional"))
      (node (ref "J2") (pin "5") (pinfunction "5_5") (pintype "passive"))
    )
    (net (code "38") (name "I_SENSE_2") (class "Default")
      (node (ref "C7") (pin "2") (pinfunction "2_2") (pintype "passive"))
      (node (ref "I1") (pin "3") (pinfunction "VIOUT_3") (pintype "bidirectional"))
      (node (ref "J2") (pin "7") (pinfunction "7_7") (pintype "passive"))
    )
    (net (code "39") (name "I_SENSE_3") (class "Default")
      (node (ref "C9") (pin "2") (pinfunction "2_2") (pintype "passive"))
      (node (ref "I2") (pin "3") (pinfunction "VIOUT_3") (pintype "bidirectional"))
      (node (ref "J2") (pin "9") (pinfunction "9_9") (pintype "passive"))
    )
    (net (code "40") (name "Net-(C12-Pad2)") (class "Default")
      (node (ref "C12") (pin "2") (pinfunction "2_2") (pintype "passive"))
      (node (ref "R36") (pin "1") (pinfunction "1_1") (pintype "passive"))
    )
    (net (code "41") (name "Net-(D1-K)") (class "Default")
      (node (ref "D1") (pin "3") (pinfunction "K_3") (pintype "passive"))
      (node (ref "L2") (pin "2") (pinfunction "2_2") (pintype "passive"))
      (node (ref "R37") (pin "2") (pinfunction "3_2") (pintype "passive"))
    )
    (net (code "42") (name "Net-(LED1-PadA)") (class "Default")
      (node (ref "LED1") (pin "A") (pinfunction "A_A") (pintype "passive"))
      (node (ref "R10") (pin "2") (pinfunction "2_2") (pintype "passive"))
    )
    (net (code "43") (name "Net-(LED2-PadA)") (class "Default")
      (node (ref "LED2") (pin "A") (pinfunction "A_A") (pintype "passive"))
      (node (ref "R11") (pin "2") (pinfunction "2_2") (pintype "passive"))
    )
    (net (code "44") (name "Net-(LED3-PadA)") (class "Default")
      (node (ref "LED3") (pin "A") (pinfunction "A_A") (pintype "passive"))
      (node (ref "R12") (pin "2") (pinfunction "2_2") (pintype "passive"))
    )
    (net (code "45") (name "Net-(LED4-PadA)") (class "Default")
      (node (ref "LED4") (pin "A") (pinfunction "A_A") (pintype "passive"))
      (node (ref "R21") (pin "2") (pinfunction "2_2") (pintype "passive"))
    )
    (net (code "46") (name "Net-(LED5-PadA)") (class "Default")
      (node (ref "LED5") (pin "A") (pinfunction "A_A") (pintype "passive"))
      (node (ref "R22") (pin "2") (pinfunction "2_2") (pintype "passive"))
    )
    (net (code "47") (name "Net-(LED7-PadA)") (class "Default")
      (node (ref "LED7") (pin "A") (pinfunction "A_A") (pintype "passive"))
      (node (ref "R48") (pin "2") (pinfunction "2_2") (pintype "passive"))
    )
    (net (code "48") (name "Net-(LED8-PadA)") (class "Default")
      (node (ref "LED8") (pin "A") (pinfunction "A_A") (pintype "passive"))
      (node (ref "R49") (pin "2") (pinfunction "2_2") (pintype "passive"))
    )
    (net (code "49") (name "Net-(R19-1)") (class "Default")
      (node (ref "R19") (pin "P$1") (pinfunction "1_P$1") (pintype "passive"))
      (node (ref "U9") (pin "2") (pinfunction "D_2") (pintype "passive"))
    )
    (net (code "50") (name "Net-(R20-1)") (class "Default")
      (node (ref "R20") (pin "P$1") (pinfunction "1_P$1") (pintype "passive"))
      (node (ref "U16") (pin "2") (pinfunction "D_2") (pintype "passive"))
    )
    (net (code "51") (name "Net-(R47-1)") (class "Default")
      (node (ref "R47") (pin "P$1") (pinfunction "1_P$1") (pintype "passive"))
      (node (ref "U20") (pin "2") (pinfunction "D_2") (pintype "passive"))
    )
    (net (code "52") (name "Net-(U2-HO)") (class "Default")
      (node (ref "R3") (pin "1") (pinfunction "1_1") (pintype "passive"))
      (node (ref "U2") (pin "7") (pinfunction "HO_7") (pintype "output"))
    )
    (net (code "53") (name "Net-(U2-VB)") (class "Default")
      (node (ref "C3") (pin "1") (pinfunction "1_1") (pintype "passive"))
      (node (ref "U2") (pin "8") (pinfunction "VB_8") (pintype "power_in"))
      (node (ref "U22") (pin "1") (pinfunction "1_1") (pintype "passive"))
    )
    (net (code "54") (name "Net-(U4-HO)") (class "Default")
      (node (ref "R13") (pin "1") (pinfunction "1_1") (pintype "passive"))
      (node (ref "U4") (pin "7") (pinfunction "HO_7") (pintype "output"))
    )
    (net (code "55") (name "Net-(U4-VB)") (class "Default")
      (node (ref "C5") (pin "1") (pinfunction "1_1") (pintype "passive"))
      (node (ref "U13") (pin "1") (pinfunction "1_1") (pintype "passive"))
      (node (ref "U4") (pin "8") (pinfunction "VB_8") (pintype "power_in"))
    )
    (net (code "56") (name "Net-(U10-HO)") (class "Default")
      (node (ref "R4") (pin "1") (pinfunction "1_1") (pintype "passive"))
      (node (ref "U10") (pin "7") (pinfunction "HO_7") (pintype "output"))
    )
    (net (code "57") (name "Net-(U10-VB)") (class "Default")
      (node (ref "C19") (pin "1") (pinfunction "1_1") (pintype "passive"))
      (node (ref "U10") (pin "8") (pinfunction "VB_8") (pintype "power_in"))
      (node (ref "U12") (pin "1") (pinfunction "1_1") (pintype "passive"))
    )
    (net (code "58") (name "Net-(U14-HO)") (class "Default")
      (node (ref "R15") (pin "1") (pinfunction "1_1") (pintype "passive"))
      (node (ref "U14") (pin "7") (pinfunction "HO_7") (pintype "output"))
    )
    (net (code "59") (name "Net-(U14-VB)") (class "Default")
      (node (ref "C21") (pin "1") (pinfunction "1_1") (pintype "passive"))
      (node (ref "U14") (pin "8") (pinfunction "VB_8") (pintype "power_in"))
      (node (ref "U17") (pin "1") (pinfunction "1_1") (pintype "passive"))
    )
    (net (code "60") (name "Net-(U18-HO)") (class "Default")
      (node (ref "R17") (pin "1") (pinfunction "1_1") (pintype "passive"))
      (node (ref "U18") (pin "7") (pinfunction "HO_7") (pintype "output"))
    )
    (net (code "61") (name "Net-(U18-VB)") (class "Default")
      (node (ref "C24") (pin "1") (pinfunction "1_1") (pintype "passive"))
      (node (ref "U18") (pin "8") (pinfunction "VB_8") (pintype "power_in"))
      (node (ref "U21") (pin "1") (pinfunction "1_1") (pintype "passive"))
    )
    (net (code "62") (name "Net-(U23-HO)") (class "Default")
      (node (ref "R6") (pin "1") (pinfunction "1_1") (pintype "passive"))
      (node (ref "U23") (pin "7") (pinfunction "HO_7") (pintype "output"))
    )
    (net (code "63") (name "Net-(U23-VB)") (class "Default")
      (node (ref "C25") (pin "1") (pinfunction "1_1") (pintype "passive"))
      (node (ref "U23") (pin "8") (pinfunction "VB_8") (pintype "power_in"))
      (node (ref "U26") (pin "1") (pinfunction "1_1") (pintype "passive"))
    )
    (net (code "64") (name "Net-(U27-HO)") (class "Default")
      (node (ref "R9") (pin "1") (pinfunction "1_1") (pintype "passive"))
      (node (ref "U27") (pin "7") (pinfunction "HO_7") (pintype "output"))
    )
    (net (code "65") (name "Net-(U27-VB)") (class "Default")
      (node (ref "C27") (pin "1") (pinfunction "1_1") (pintype "passive"))
      (node (ref "U27") (pin "8") (pinfunction "VB_8") (pintype "power_in"))
      (node (ref "U30") (pin "1") (pinfunction "1_1") (pintype "passive"))
    )
    (net (code "66") (name "PGND") (class "Default")
      (node (ref "C15") (pin "2") (pinfunction "2_2") (pintype "passive"))
      (node (ref "C16") (pin "2") (pinfunction "2_2") (pintype "passive"))
      (node (ref "C17") (pin "2") (pinfunction "2_2") (pintype "passive"))
      (node (ref "C18") (pin "2") (pinfunction "2_2") (pintype "passive"))
      (node (ref "D1") (pin "1") (pinfunction "A1_1") (pintype "passive"))
      (node (ref "D1") (pin "2") (pinfunction "A2_2") (pintype "passive"))
      (node (ref "U6") (pin "13") (pinfunction "PGND_13") (pintype "power_in"))
    )
    (net (code "67") (name "PGOOD") (class "Default")
      (node (ref "J2") (pin "10") (pinfunction "10_10") (pintype "passive"))
      (node (ref "R31") (pin "2") (pinfunction "2_2") (pintype "passive"))
      (node (ref "R35") (pin "1") (pinfunction "1_1") (pintype "passive"))
      (node (ref "U6") (pin "7") (pinfunction "PGOOD_7") (pintype "output"))
    )
    (net (code "68") (name "PRECHARGE_2") (class "Default")
      (node (ref "J1") (pin "10") (pinfunction "10_10") (pintype "passive"))
      (node (ref "U4") (pin "2") (pinfunction "~{IN}_2") (pintype "input"))
    )
    (net (code "69") (name "PRECHARGE_3") (class "Default")
      (node (ref "J1") (pin "8") (pinfunction "8_8") (pintype "passive"))
      (node (ref "U14") (pin "2") (pinfunction "~{IN}_2") (pintype "input"))
    )
    (net (code "70") (name "PRECHARGE_4") (class "Default")
      (node (ref "J1") (pin "6") (pinfunction "6_6") (pintype "passive"))
      (node (ref "U18") (pin "2") (pinfunction "~{IN}_2") (pintype "input"))
    )
    (net (code "71") (name "REF") (class "Default")
      (node (ref "J2") (pin "3") (pinfunction "3_3") (pintype "passive"))
    )
    (net (code "72") (name "RST0") (class "Default")
      (node (ref "J1") (pin "13") (pinfunction "13_13") (pintype "passive"))
    )
    (net (code "73") (name "RST1") (class "Default")
      (node (ref "J2") (pin "13") (pinfunction "13_13") (pintype "passive"))
    )
    (net (code "74") (name "RX0") (class "Default")
      (node (ref "J1") (pin "14") (pinfunction "14_14") (pintype "passive"))
    )
    (net (code "75") (name "SENSE") (class "Default")
      (node (ref "R37") (pin "3") (pinfunction "2_3") (pintype "passive"))
      (node (ref "R38") (pin "1") (pinfunction "1_1") (pintype "passive"))
      (node (ref "U6") (pin "10") (pinfunction "SENSE_10") (pintype "input"))
    )
    (net (code "76") (name "SGND") (class "Default")
      (node (ref "C12") (pin "1") (pinfunction "1_1") (pintype "passive"))
      (node (ref "C13") (pin "1") (pinfunction "1_1") (pintype "passive"))
      (node (ref "R29") (pin "1") (pinfunction "1_1") (pintype "passive"))
      (node (ref "R30") (pin "1") (pinfunction "1_1") (pintype "passive"))
      (node (ref "R31") (pin "1") (pinfunction "1_1") (pintype "passive"))
      (node (ref "R32") (pin "1") (pinfunction "1_1") (pintype "passive"))
      (node (ref "U6") (pin "3") (pinfunction "SGND_3") (pintype "power_in"))
    )
    (net (code "77") (name "SS") (class "Default")
      (node (ref "R29") (pin "2") (pinfunction "2_2") (pintype "passive"))
      (node (ref "R33") (pin "1") (pinfunction "1_1") (pintype "passive"))
      (node (ref "U6") (pin "4") (pinfunction "SS_4") (pintype "input"))
    )
    (net (code "78") (name "SWITCH_1") (class "Default")
      (node (ref "J1") (pin "11") (pinfunction "11_11") (pintype "passive"))
      (node (ref "U10") (pin "2") (pinfunction "~{IN}_2") (pintype "input"))
    )
    (net (code "79") (name "SWITCH_2") (class "Default")
      (node (ref "J1") (pin "9") (pinfunction "9_9") (pintype "passive"))
      (node (ref "U2") (pin "2") (pinfunction "~{IN}_2") (pintype "input"))
    )
    (net (code "80") (name "SWITCH_3") (class "Default")
      (node (ref "J1") (pin "7") (pinfunction "7_7") (pintype "passive"))
      (node (ref "U23") (pin "2") (pinfunction "~{IN}_2") (pintype "input"))
    )
    (net (code "81") (name "SWITCH_4") (class "Default")
      (node (ref "J1") (pin "5") (pinfunction "5_5") (pintype "passive"))
      (node (ref "U27") (pin "2") (pinfunction "~{IN}_2") (pintype "input"))
    )
    (net (code "82") (name "S_PRECHARGE_2") (class "Default")
      (node (ref "C5") (pin "2") (pinfunction "2_2") (pintype "passive"))
      (node (ref "LED4") (pin "C") (pinfunction "C_C") (pintype "passive"))
      (node (ref "R1") (pin "2") (pinfunction "2_2") (pintype "passive"))
      (node (ref "U4") (pin "6") (pinfunction "VS_6") (pintype "power_in"))
      (node (ref "U5") (pin "3") (pinfunction "S_3") (pintype "passive"))
      (node (ref "U9") (pin "3") (pinfunction "S_3") (pintype "passive"))
    )
    (net (code "83") (name "S_PRECHARGE_3") (class "Default")
      (node (ref "C21") (pin "2") (pinfunction "2_2") (pintype "passive"))
      (node (ref "LED5") (pin "C") (pinfunction "C_C") (pintype "passive"))
      (node (ref "R14") (pin "2") (pinfunction "2_2") (pintype "passive"))
      (node (ref "U14") (pin "6") (pinfunction "VS_6") (pintype "power_in"))
      (node (ref "U15") (pin "3") (pinfunction "S_3") (pintype "passive"))
      (node (ref "U16") (pin "3") (pinfunction "S_3") (pintype "passive"))
    )
    (net (code "84") (name "S_PRECHARGE_4") (class "Default")
      (node (ref "C24") (pin "2") (pinfunction "2_2") (pintype "passive"))
      (node (ref "LED8") (pin "C") (pinfunction "C_C") (pintype "passive"))
      (node (ref "R16") (pin "2") (pinfunction "2_2") (pintype "passive"))
      (node (ref "U18") (pin "6") (pinfunction "VS_6") (pintype "power_in"))
      (node (ref "U19") (pin "3") (pinfunction "S_3") (pintype "passive"))
      (node (ref "U20") (pin "3") (pinfunction "S_3") (pintype "passive"))
    )
    (net (code "85") (name "S_SWITCH_1") (class "Default")
      (node (ref "C19") (pin "2") (pinfunction "2_2") (pintype "passive"))
      (node (ref "LED1") (pin "C") (pinfunction "C_C") (pintype "passive"))
      (node (ref "R7") (pin "2") (pinfunction "2_2") (pintype "passive"))
      (node (ref "U1") (pin "3") (pinfunction "S_3") (pintype "passive"))
      (node (ref "U10") (pin "6") (pinfunction "VS_6") (pintype "power_in"))
      (node (ref "U11") (pin "3") (pinfunction "S_3") (pintype "passive"))
    )
    (net (code "86") (name "S_SWITCH_2") (class "Default")
      (node (ref "C3") (pin "2") (pinfunction "2_2") (pintype "passive"))
      (node (ref "LED2") (pin "C") (pinfunction "C_C") (pintype "passive"))
      (node (ref "R2") (pin "2") (pinfunction "2_2") (pintype "passive"))
      (node (ref "U2") (pin "6") (pinfunction "VS_6") (pintype "power_in"))
      (node (ref "U3") (pin "3") (pinfunction "S_3") (pintype "passive"))
      (node (ref "U8") (pin "3") (pinfunction "S_3") (pintype "passive"))
    )
    (net (code "87") (name "S_SWITCH_3") (class "Default")
      (node (ref "C25") (pin "2") (pinfunction "2_2") (pintype "passive"))
      (node (ref "LED3") (pin "C") (pinfunction "C_C") (pintype "passive"))
      (node (ref "R5") (pin "2") (pinfunction "2_2") (pintype "passive"))
      (node (ref "U23") (pin "6") (pinfunction "VS_6") (pintype "power_in"))
      (node (ref "U24") (pin "3") (pinfunction "S_3") (pintype "passive"))
      (node (ref "U25") (pin "3") (pinfunction "S_3") (pintype "passive"))
    )
    (net (code "88") (name "S_SWITCH_4") (class "Default")
      (node (ref "C27") (pin "2") (pinfunction "2_2") (pintype "passive"))
      (node (ref "LED7") (pin "C") (pinfunction "C_C") (pintype "passive"))
      (node (ref "R8") (pin "2") (pinfunction "2_2") (pintype "passive"))
      (node (ref "U27") (pin "6") (pinfunction "VS_6") (pintype "power_in"))
      (node (ref "U28") (pin "3") (pinfunction "S_3") (pintype "passive"))
      (node (ref "U29") (pin "3") (pinfunction "S_3") (pintype "passive"))
    )
    (net (code "89") (name "TX1") (class "Default")
      (node (ref "J1") (pin "15") (pinfunction "15_15") (pintype "passive"))
    )
    (net (code "90") (name "VFB") (class "Default")
      (node (ref "R30") (pin "2") (pinfunction "2_2") (pintype "passive"))
      (node (ref "R34") (pin "1") (pinfunction "1_1") (pintype "passive"))
      (node (ref "U6") (pin "5") (pinfunction "VFB_5") (pintype "output"))
    )
    (net (code "91") (name "VIN") (class "Default")
      (node (ref "J2") (pin "15") (pinfunction "15_15") (pintype "passive"))
    )
    (net (code "92") (name "VOUT") (class "Default")
      (node (ref "C18") (pin "1") (pinfunction "1_1") (pintype "passive"))
      (node (ref "R34") (pin "2") (pinfunction "2_2") (pintype "passive"))
      (node (ref "R35") (pin "2") (pinfunction "2_2") (pintype "passive"))
    )
    (net (code "93") (name "V_SENSE_1") (class "Default")
      (node (ref "J2") (pin "4") (pinfunction "4_4") (pintype "passive"))
      (node (ref "R23") (pin "2") (pinfunction "2_2") (pintype "passive"))
      (node (ref "R26") (pin "1") (pinfunction "1_1") (pintype "passive"))
    )
    (net (code "94") (name "V_SENSE_2") (class "Default")
      (node (ref "J2") (pin "6") (pinfunction "6_6") (pintype "passive"))
      (node (ref "R24") (pin "2") (pinfunction "2_2") (pintype "passive"))
      (node (ref "R27") (pin "1") (pinfunction "1_1") (pintype "passive"))
    )
    (net (code "95") (name "V_SENSE_3") (class "Default")
      (node (ref "J2") (pin "8") (pinfunction "8_8") (pintype "passive"))
      (node (ref "R25") (pin "2") (pinfunction "2_2") (pintype "passive"))
      (node (ref "R28") (pin "1") (pinfunction "1_1") (pintype "passive"))
    )
    (net (code "96") (name "WORM_BUS+") (class "Default")
      (node (ref "D9") (pin "C") (pinfunction "C_C") (pintype "passive"))
      (node (ref "R20") (pin "P$2") (pinfunction "2_P$2") (pintype "passive"))
      (node (ref "U25") (pin "2") (pinfunction "D_2") (pintype "passive"))
    )
    (net (code "97") (name "unconnected-(U2-NC-Pad5)") (class "Default")
      (node (ref "U2") (pin "5") (pinfunction "NC_5") (pintype "no_connect"))
    )
    (net (code "98") (name "unconnected-(U2-NC_2-Pad4)") (class "Default")
      (node (ref "U2") (pin "4") (pinfunction "NC_2_4") (pintype "no_connect"))
    )
    (net (code "99") (name "unconnected-(U4-NC-Pad5)") (class "Default")
      (node (ref "U4") (pin "5") (pinfunction "NC_5") (pintype "no_connect"))
    )
    (net (code "100") (name "unconnected-(U4-NC_2-Pad4)") (class "Default")
      (node (ref "U4") (pin "4") (pinfunction "NC_2_4") (pintype "no_connect"))
    )
    (net (code "101") (name "unconnected-(U6-PLLIN{slash}MODE-Pad1)") (class "Default")
      (node (ref "U6") (pin "1") (pinfunction "PLLIN/MODE_1") (pintype "input"))
    )
    (net (code "102") (name "unconnected-(U10-NC-Pad5)") (class "Default")
      (node (ref "U10") (pin "5") (pinfunction "NC_5") (pintype "no_connect"))
    )
    (net (code "103") (name "unconnected-(U10-NC_2-Pad4)") (class "Default")
      (node (ref "U10") (pin "4") (pinfunction "NC_2_4") (pintype "no_connect"))
    )
    (net (code "104") (name "unconnected-(U14-NC-Pad5)") (class "Default")
      (node (ref "U14") (pin "5") (pinfunction "NC_5") (pintype "no_connect"))
    )
    (net (code "105") (name "unconnected-(U14-NC_2-Pad4)") (class "Default")
      (node (ref "U14") (pin "4") (pinfunction "NC_2_4") (pintype "no_connect"))
    )
    (net (code "106") (name "unconnected-(U18-NC-Pad5)") (class "Default")
      (node (ref "U18") (pin "5") (pinfunction "NC_5") (pintype "no_connect"))
    )
    (net (code "107") (name "unconnected-(U18-NC_2-Pad4)") (class "Default")
      (node (ref "U18") (pin "4") (pinfunction "NC_2_4") (pintype "no_connect"))
    )
    (net (code "108") (name "unconnected-(U23-NC-Pad5)") (class "Default")
      (node (ref "U23") (pin "5") (pinfunction "NC_5") (pintype "no_connect"))
    )
    (net (code "109") (name "unconnected-(U23-NC_2-Pad4)") (class "Default")
      (node (ref "U23") (pin "4") (pinfunction "NC_2_4") (pintype "no_connect"))
    )
    (net (code "110") (name "unconnected-(U27-NC-Pad5)") (class "Default")
      (node (ref "U27") (pin "5") (pinfunction "NC_5") (pintype "no_connect"))
    )
    (net (code "111") (name "unconnected-(U27-NC_2-Pad4)") (class "Default")
      (node (ref "U27") (pin "4") (pinfunction "NC_2_4") (pintype "no_connect"))
    )
  )
)
